# Flyback.net
KiCad netlist of a schematic drawn in Altium Designer
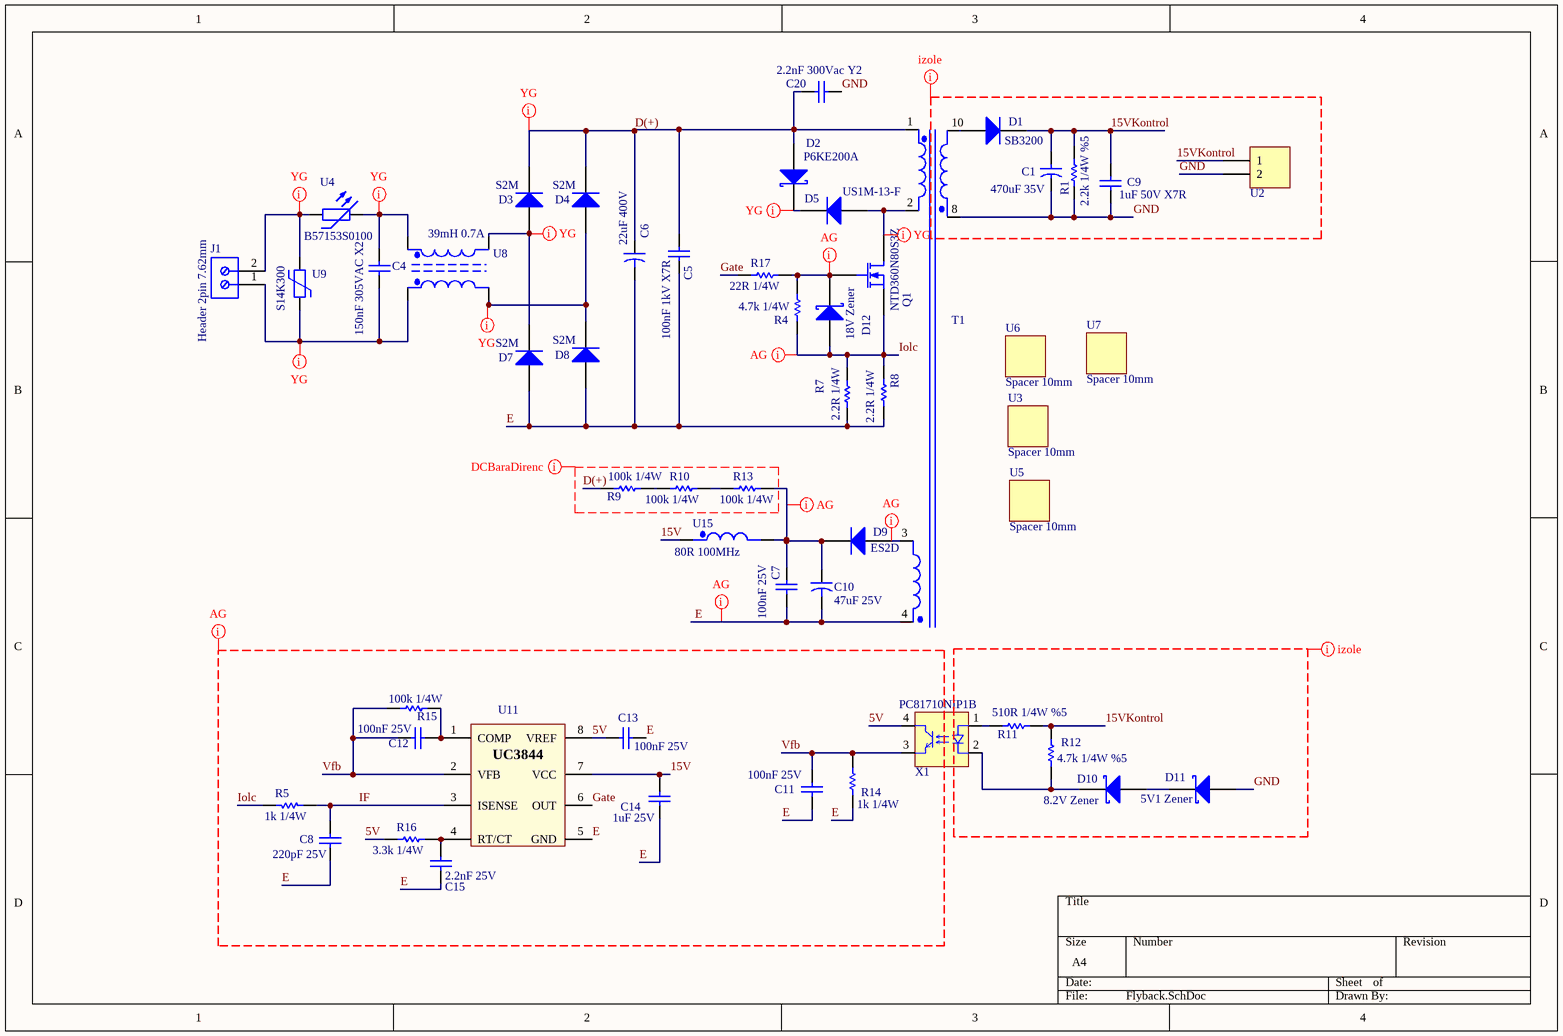
[diagram p0: Flyback.SchDoc]

(export (version "E")
  (design (tool "Eeschema 10.0.6"))
  (components
    (comp (ref "C1")
      (value "470uF 35V")
      (footprint "CAPPRD500W60D1025H1750")
      (description "860040475008")
      (fields (field (name "PUBLISHER") "Altium Limited"))
      (libsource (lib "GenelKutuphane") (part "C 470uF 35V 1.76A 28mOhm"))
    )
    (comp (ref "C4")
      (value "150nF 305VAC X2")
      (footprint "CFR F15 L18 B6 H12")
      (description "MPX154K305E")
      (fields (field (name "PART NUMBER") "890273322005CS") (field (name "PUBLISHER") "Wurth Elektronik"))
      (libsource (lib "GenelKutuphane") (part "Cap 150nF 305VAC X2"))
    )
    (comp (ref "C5")
      (value "100nF 1kV X7R")
      (footprint "RCE7U2J333J5B1H03B")
      (description "RDER73A104K5B1H03B")
      (fields (field (name "PUBLISHER") "Altium Limited"))
      (libsource (lib "GenelKutuphane") (part "C Seramik 100nF 1kV X7R 5mm"))
    )
    (comp (ref "C6")
      (value "22uF 400V")
      (footprint "GenelKutuphane:22uF 400V")
      (description "860241378003")
      (fields
        (field (name "MANUFACTURER_PART_NUMBER") "TPSE107K020R0150")
        (field (name "MOUSER PART NUMBER") "581-TPSE107K020R0150")
      )
      (libsource (lib "GenelKutuphane") (part "C 22uF 400V 537mArms"))
    )
    (comp (ref "C7")
      (value "100nF 25V")
      (footprint "1206")
      (description "SMD 1206")
      (libsource (lib "GenelKutuphane") (part "C 1206"))
    )
    (comp (ref "C8")
      (value "220pF 25V")
      (footprint "1206")
      (description "SMD 1206")
      (libsource (lib "GenelKutuphane") (part "C 1206"))
    )
    (comp (ref "C9")
      (value "1uF 50V X7R")
      (footprint "1206")
      (description "490-3908-2-ND")
      (libsource (lib "GenelKutuphane") (part "C 1206"))
    )
    (comp (ref "C10")
      (value "47uF 25V")
      (footprint "CAPPRD200W50D525H1250")
      (description "25YXJ47MTA5X11")
      (libsource (lib "GenelKutuphane") (part "C 47uF 25V 250mArms 400mOhm"))
    )
    (comp (ref "C11")
      (value "100nF 25V")
      (footprint "1206")
      (description "SMD 1206")
      (libsource (lib "GenelKutuphane") (part "C 1206"))
    )
    (comp (ref "C12")
      (value "100nF 25V")
      (footprint "1206")
      (description "SMD 1206")
      (libsource (lib "GenelKutuphane") (part "C 1206"))
    )
    (comp (ref "C13")
      (value "100nF 25V")
      (footprint "1206")
      (description "SMD 1206")
      (libsource (lib "GenelKutuphane") (part "C 1206"))
    )
    (comp (ref "C14")
      (value "1uF 25V")
      (footprint "1206")
      (description "SMD 1206")
      (libsource (lib "GenelKutuphane") (part "C 1206"))
    )
    (comp (ref "C15")
      (value "2.2nF 25V")
      (footprint "1206")
      (description "SMD 1206")
      (libsource (lib "GenelKutuphane") (part "C 1206"))
    )
    (comp (ref "C20")
      (value "2.2nF 300Vac Y2")
      (footprint "4x13x9")
      (description "B32021A3222")
      (fields (field (name "PUBLISHER") "Altium Limited"))
      (libsource (lib "GenelKutuphane") (part "Cap Y2 2.2nF MKP TDK"))
    )
    (comp (ref "D1")
      (value "SB3200")
      (footprint "GenelKutuphane:DO-201AD -Dik")
      (description "DO-201AD")
      (libsource (lib "GenelKutuphane") (part "D MUR460"))
    )
    (comp (ref "D2")
      (value "P6KE200A")
      (footprint "DO-15((DO-204AC)")
      (description "497-13419-1-ND")
      (fields (field (name "PUBLISHER") "Altium Limited"))
      (libsource (lib "GenelKutuphane") (part "TVS 200V DO-15"))
    )
    (comp (ref "D3")
      (value "S2M")
      (footprint "DO-214AA(SMB)")
      (description "DO-214AA(SMB)")
      (libsource (lib "GenelKutuphane") (part "1N4007"))
    )
    (comp (ref "D4")
      (value "S2M")
      (footprint "DO-214AA(SMB)")
      (description "DO-214AA(SMB)")
      (libsource (lib "GenelKutuphane") (part "1N4007"))
    )
    (comp (ref "D5")
      (value "US1M-13-F")
      (footprint "DO-214AA(SMB)")
      (description "US1M-FDICT-ND")
      (libsource (lib "GenelKutuphane") (part "ES2D"))
    )
    (comp (ref "D7")
      (value "S2M")
      (footprint "DO-214AA(SMB)")
      (description "DO-214AA(SMB)")
      (libsource (lib "GenelKutuphane") (part "1N4007"))
    )
    (comp (ref "D8")
      (value "S2M")
      (footprint "DO-214AA(SMB)")
      (description "DO-214AA(SMB)")
      (libsource (lib "GenelKutuphane") (part "1N4007"))
    )
    (comp (ref "D9")
      (value "ES2D")
      (footprint "DO-214AA(SMB)")
      (description "ES2DFSCT-ND")
      (libsource (lib "GenelKutuphane") (part "ES2D"))
    )
    (comp (ref "D10")
      (value "8.2V Zener")
      (footprint "GenelKutuphane:SOD-123")
      (description "SOD-123")
      (fields (field (name "PUBLISHER") "Altium Limited"))
      (libsource (lib "GenelKutuphane") (part "Zener 1/4W"))
    )
    (comp (ref "D11")
      (value "5V1 Zener")
      (footprint "SOD-123")
      (description "SOD-123")
      (fields (field (name "PUBLISHER") "Altium Limited"))
      (libsource (lib "GenelKutuphane") (part "Zener 1W"))
    )
    (comp (ref "D12")
      (value "18V Zener")
      (footprint "GenelKutuphane:SOD-123")
      (description "SOD-123")
      (fields (field (name "PUBLISHER") "Altium Limited"))
      (libsource (lib "GenelKutuphane") (part "Zener 0.5W"))
    )
    (comp (ref "J1")
      (value "Header 2pin 7.62mm")
      (footprint "Header 2 Pin 7.62mm Vidalı")
      (description "691214410002")
      (fields (field (name "PART NUMBER") "691218410002") (field (name "PUBLISHER") "Wurth Elektronik"))
      (libsource (lib "GenelKutuphane") (part "Header 2pin 7.62mm Vidalı"))
    )
    (comp (ref "Q1")
      (value "NTD360N80S3Z")
      (footprint "DPAK IGBT")
      (description "DPAK")
      (fields (field (name "PUBLISHER") "Altium Limited"))
      (libsource (lib "GenelKutuphane") (part "MOSFET DPAK"))
    )
    (comp (ref "R1")
      (value "2.2k 1/4W %5")
      (footprint "R 1206")
      (description "311-2.2KERTR-ND")
      (libsource (lib "GenelKutuphane") (part "R 1206"))
    )
    (comp (ref "R4")
      (value "4.7k 1/4W")
      (footprint "R 1206")
      (description "SMD 1206")
      (libsource (lib "GenelKutuphane") (part "1/4W Karbon"))
    )
    (comp (ref "R5")
      (value "1k 1/4W")
      (footprint "R 1206")
      (description "SMD 1206/RC1206JR-07330RL/Digikey")
      (libsource (lib "GenelKutuphane") (part "R 1206"))
    )
    (comp (ref "R7")
      (value "2.2R 1/4W")
      (footprint "R 1206")
      (description "SMD 1206")
      (libsource (lib "GenelKutuphane") (part "R 1206"))
    )
    (comp (ref "R8")
      (value "2.2R 1/4W")
      (footprint "R 1206")
      (description "SMD 1206")
      (libsource (lib "GenelKutuphane") (part "R 1206"))
    )
    (comp (ref "R9")
      (value "100k 1/4W")
      (footprint "R 1206")
      (description "SMD 126")
      (libsource (lib "ramazanlib") (part "R 1206"))
    )
    (comp (ref "R10")
      (value "100k 1/4W")
      (footprint "R 1206")
      (description "SMD 126")
      (libsource (lib "ramazanlib") (part "R 1206"))
    )
    (comp (ref "R11")
      (value "510R 1/4W %5")
      (footprint "R 1206")
      (description "311-100NLCT-ND")
      (libsource (lib "GenelKutuphane") (part "R 1206"))
    )
    (comp (ref "R12")
      (value "4.7k 1/4W %5")
      (footprint "R 1206")
      (description "311-4.7KERCT-ND")
      (libsource (lib "GenelKutuphane") (part "R 1206"))
    )
    (comp (ref "R13")
      (value "100k 1/4W")
      (footprint "R 1206")
      (description "SMD 126")
      (libsource (lib "ramazanlib") (part "R 1206"))
    )
    (comp (ref "R14")
      (value "1k 1/4W")
      (footprint "R 1206")
      (description "SMD 1206")
      (libsource (lib "GenelKutuphane") (part "R 1206"))
    )
    (comp (ref "R15")
      (value "100k 1/4W")
      (footprint "R 1206")
      (description "SMD 1206")
      (libsource (lib "GenelKutuphane") (part "R 1206"))
    )
    (comp (ref "R16")
      (value "3.3k 1/4W")
      (footprint "R 1206")
      (description "SMD 1206")
      (libsource (lib "GenelKutuphane") (part "R 1206"))
    )
    (comp (ref "R17")
      (value "22R 1/4W")
      (footprint "R 1206")
      (description "SMD 1206")
      (libsource (lib "ramazanlib") (part "R 1206"))
    )
    (comp (ref "T1")
      (value "SMPS Tr")
      (footprint "SMPS Tr3")
      (fields (field (name "PUBLISHER") "Altium Limited"))
      (libsource (lib "GenelKutuphane") (part "SMPS Tr EF25"))
    )
    (comp (ref "U2")
      (value "Terminal Blok 2 Pin 2.54mm")
      (footprint "Header 2pin 2.54mm Vidalı")
      (description "691210910002")
      (fields (field (name "PUBLISHER") "Altium Limited"))
      (libsource (lib "GenelKutuphane") (part "Header 2 Pin 2.54mm Vidalı"))
    )
    (comp (ref "U3")
      (value "Spacer 10mm")
      (footprint "Spacer 10mm Sogutucu")
      (description "10mm")
      (fields (field (name "PUBLISHER") "Altium Limited"))
      (libsource (lib "GenelKutuphane") (part "Spacer 10mm"))
    )
    (comp (ref "U4")
      (value "B57153S0100")
      (footprint "NTC B57153S0100")
      (description "495-2076-ND")
      (fields (field (name "PUBLISHER") "Altium Limited"))
      (libsource (lib "GenelKutuphane") (part "NTC B57153S0100"))
    )
    (comp (ref "U5")
      (value "Spacer 10mm")
      (footprint "Spacer 10mm Sogutucu")
      (description "10mm")
      (fields (field (name "PUBLISHER") "Altium Limited"))
      (libsource (lib "GenelKutuphane") (part "Spacer 10mm"))
    )
    (comp (ref "U6")
      (value "Spacer 10mm")
      (footprint "Spacer 10mm Sogutucu")
      (description "10mm")
      (fields (field (name "PUBLISHER") "Altium Limited"))
      (libsource (lib "GenelKutuphane") (part "Spacer 10mm"))
    )
    (comp (ref "U7")
      (value "Spacer 10mm")
      (footprint "Spacer 10mm Sogutucu")
      (description "10mm")
      (fields (field (name "PUBLISHER") "Altium Limited"))
      (libsource (lib "GenelKutuphane") (part "Spacer 10mm"))
    )
    (comp (ref "U8")
      (value "39mH 0.7A")
      (footprint "EMC SMPS TDK")
      (description "B82732R2701B030")
      (libsource (lib "GenelKutuphane") (part "EMC SMPS TDK 39mH 0.7A"))
    )
    (comp (ref "U9")
      (value "S14K300")
      (footprint "GenelKutuphane:Varistor630V")
      (description "495-1442-ND")
      (fields (field (name "PUBLISHER") "Altium Limited"))
      (libsource (lib "GenelKutuphane") (part "Varistor  S14K175"))
    )
    (comp (ref "U11")
      (value "UC3844")
      (footprint "SOIC-OA8_L")
      (description "SOIC8")
      (libsource (lib "GenelKutuphane") (part "UC3844"))
    )
    (comp (ref "U15")
      (value "80R 100MHz")
      (footprint "1206 Bead")
      (description "732-1629-1-ND")
      (libsource (lib "GenelKutuphane") (part "Bead 1206"))
    )
    (comp (ref "X1")
      (value "PC81710NIP1B")
      (footprint "PC817 SMD")
      (description "1855-1014-1-ND")
      (libsource (lib "GenelKutuphane") (part "PC817"))
    )
  )
  (nets
    (net (code "1") (name "/5V") (class "Default")
      (node (ref "C13") (pin "2") (pinfunction "2_2") (pintype "passive"))
      (node (ref "R16") (pin "1") (pinfunction "1_1") (pintype "passive"))
      (node (ref "U11") (pin "8") (pinfunction "VREF_8") (pintype "passive"))
      (node (ref "X1") (pin "4") (pinfunction "C_4") (pintype "passive"))
    )
    (net (code "2") (name "/15V") (class "Default")
      (node (ref "C14") (pin "2") (pinfunction "2_2") (pintype "passive"))
      (node (ref "U11") (pin "7") (pinfunction "VCC_7") (pintype "passive"))
      (node (ref "U15") (pin "1") (pinfunction "1_1") (pintype "passive"))
    )
    (net (code "3") (name "/15VKontrol") (class "Default")
      (node (ref "C1") (pin "1") (pinfunction "1_1") (pintype "passive"))
      (node (ref "C9") (pin "2") (pinfunction "2_2") (pintype "passive"))
      (node (ref "D1") (pin "2") (pinfunction "K_2") (pintype "passive"))
      (node (ref "R1") (pin "2") (pinfunction "2_2") (pintype "passive"))
      (node (ref "R11") (pin "1") (pinfunction "1_1") (pintype "passive"))
      (node (ref "R12") (pin "1") (pinfunction "1_1") (pintype "passive"))
      (node (ref "U2") (pin "1") (pinfunction "1_1") (pintype "passive"))
    )
    (net (code "4") (name "/D(+)") (class "Default")
      (node (ref "C20") (pin "1") (pinfunction "1_1") (pintype "passive"))
      (node (ref "C5") (pin "2") (pinfunction "2_2") (pintype "passive"))
      (node (ref "C6") (pin "1") (pinfunction "1_1") (pintype "passive"))
      (node (ref "D2") (pin "1") (pinfunction "A_1") (pintype "passive"))
      (node (ref "D3") (pin "2") (pinfunction "K_2") (pintype "passive"))
      (node (ref "D4") (pin "2") (pinfunction "K_2") (pintype "passive"))
      (node (ref "R9") (pin "2") (pinfunction "2_2") (pintype "passive"))
      (node (ref "T1") (pin "1") (pinfunction "Pri+_1") (pintype "passive"))
    )
    (net (code "5") (name "/E") (class "Default")
      (node (ref "C10") (pin "2") (pinfunction "2_2") (pintype "passive"))
      (node (ref "C11") (pin "1") (pinfunction "1_1") (pintype "passive"))
      (node (ref "C13") (pin "1") (pinfunction "1_1") (pintype "passive"))
      (node (ref "C14") (pin "1") (pinfunction "1_1") (pintype "passive"))
      (node (ref "C15") (pin "1") (pinfunction "1_1") (pintype "passive"))
      (node (ref "C5") (pin "1") (pinfunction "1_1") (pintype "passive"))
      (node (ref "C6") (pin "2") (pinfunction "2_2") (pintype "passive"))
      (node (ref "C7") (pin "1") (pinfunction "1_1") (pintype "passive"))
      (node (ref "C8") (pin "1") (pinfunction "1_1") (pintype "passive"))
      (node (ref "D7") (pin "1") (pinfunction "A_1") (pintype "passive"))
      (node (ref "D8") (pin "1") (pinfunction "A_1") (pintype "passive"))
      (node (ref "R14") (pin "1") (pinfunction "1_1") (pintype "passive"))
      (node (ref "R7") (pin "1") (pinfunction "1_1") (pintype "passive"))
      (node (ref "R8") (pin "1") (pinfunction "1_1") (pintype "passive"))
      (node (ref "T1") (pin "4") (pinfunction "Sec3-_4") (pintype "passive"))
      (node (ref "U11") (pin "5") (pinfunction "GND_5") (pintype "power_in"))
    )
    (net (code "6") (name "/GND") (class "Default")
      (node (ref "C1") (pin "2") (pinfunction "2_2") (pintype "passive"))
      (node (ref "C20") (pin "2") (pinfunction "2_2") (pintype "passive"))
      (node (ref "C9") (pin "1") (pinfunction "1_1") (pintype "passive"))
      (node (ref "D11") (pin "1") (pinfunction "A_1") (pintype "passive"))
      (node (ref "R1") (pin "1") (pinfunction "1_1") (pintype "passive"))
      (node (ref "T1") (pin "8") (pinfunction "8_8") (pintype "passive"))
      (node (ref "U2") (pin "2") (pinfunction "2_2") (pintype "passive"))
    )
    (net (code "7") (name "/Gate") (class "Default")
      (node (ref "R17") (pin "1") (pinfunction "1_1") (pintype "passive"))
      (node (ref "U11") (pin "6") (pinfunction "OUT_6") (pintype "power_in"))
    )
    (net (code "8") (name "/IF") (class "Default")
      (node (ref "C8") (pin "2") (pinfunction "2_2") (pintype "passive"))
      (node (ref "R5") (pin "1") (pinfunction "1_1") (pintype "passive"))
      (node (ref "U11") (pin "3") (pinfunction "ISENSE_3") (pintype "passive"))
    )
    (net (code "9") (name "/Iolc") (class "Default")
      (node (ref "D12") (pin "1") (pinfunction "A_1") (pintype "passive"))
      (node (ref "Q1") (pin "3") (pinfunction "S_3") (pintype "passive"))
      (node (ref "R4") (pin "2") (pinfunction "2_2") (pintype "passive"))
      (node (ref "R5") (pin "2") (pinfunction "2_2") (pintype "passive"))
      (node (ref "R7") (pin "2") (pinfunction "2_2") (pintype "passive"))
      (node (ref "R8") (pin "2") (pinfunction "2_2") (pintype "passive"))
    )
    (net (code "10") (name "/Vfb") (class "Default")
      (node (ref "C11") (pin "2") (pinfunction "2_2") (pintype "passive"))
      (node (ref "C12") (pin "1") (pinfunction "1_1") (pintype "passive"))
      (node (ref "R14") (pin "2") (pinfunction "2_2") (pintype "passive"))
      (node (ref "R15") (pin "1") (pinfunction "1_1") (pintype "passive"))
      (node (ref "U11") (pin "2") (pinfunction "VFB_2") (pintype "passive"))
      (node (ref "X1") (pin "3") (pinfunction "E_3") (pintype "passive"))
    )
    (net (code "11") (name "Net-(C4-Pad1)") (class "Default")
      (node (ref "C4") (pin "1") (pinfunction "1_1") (pintype "passive"))
      (node (ref "J1") (pin "1") (pinfunction "1_1") (pintype "passive"))
      (node (ref "U8") (pin "1") (pinfunction "1_1") (pintype "passive"))
      (node (ref "U9") (pin "1") (pinfunction "1_1") (pintype "passive"))
    )
    (net (code "12") (name "Net-(C4-Pad2)") (class "Default")
      (node (ref "C4") (pin "2") (pinfunction "2_2") (pintype "passive"))
      (node (ref "U4") (pin "2") (pinfunction "2_2") (pintype "passive"))
      (node (ref "U8") (pin "2") (pinfunction "2_2") (pintype "passive"))
    )
    (net (code "13") (name "Net-(D1-A)") (class "Default")
      (node (ref "D1") (pin "1") (pinfunction "A_1") (pintype "passive"))
      (node (ref "T1") (pin "10") (pinfunction "Sec1+_10") (pintype "passive"))
    )
    (net (code "14") (name "Net-(D2-K)") (class "Default")
      (node (ref "D2") (pin "2") (pinfunction "K_2") (pintype "passive"))
      (node (ref "D5") (pin "2") (pinfunction "K_2") (pintype "passive"))
    )
    (net (code "15") (name "Net-(D3-A)") (class "Default")
      (node (ref "D3") (pin "1") (pinfunction "A_1") (pintype "passive"))
      (node (ref "D7") (pin "2") (pinfunction "K_2") (pintype "passive"))
      (node (ref "U8") (pin "3") (pinfunction "3_3") (pintype "passive"))
    )
    (net (code "16") (name "Net-(D4-A)") (class "Default")
      (node (ref "D4") (pin "1") (pinfunction "A_1") (pintype "passive"))
      (node (ref "D8") (pin "2") (pinfunction "K_2") (pintype "passive"))
      (node (ref "U8") (pin "4") (pinfunction "4_4") (pintype "passive"))
    )
    (net (code "17") (name "Net-(D5-A)") (class "Default")
      (node (ref "D5") (pin "1") (pinfunction "A_1") (pintype "passive"))
      (node (ref "Q1") (pin "2") (pinfunction "D_2") (pintype "passive"))
      (node (ref "T1") (pin "2") (pinfunction "Pri-_2") (pintype "passive"))
    )
    (net (code "18") (name "Net-(D9-A)") (class "Default")
      (node (ref "D9") (pin "1") (pinfunction "A_1") (pintype "passive"))
      (node (ref "T1") (pin "3") (pinfunction "Sec3+_3") (pintype "passive"))
    )
    (net (code "19") (name "Net-(D9-K)") (class "Default")
      (node (ref "C10") (pin "1") (pinfunction "1_1") (pintype "passive"))
      (node (ref "C7") (pin "2") (pinfunction "2_2") (pintype "passive"))
      (node (ref "D9") (pin "2") (pinfunction "K_2") (pintype "passive"))
      (node (ref "R13") (pin "1") (pinfunction "1_1") (pintype "passive"))
      (node (ref "U15") (pin "2") (pinfunction "2_2") (pintype "passive"))
    )
    (net (code "20") (name "Net-(D10-A)") (class "Default")
      (node (ref "D10") (pin "1") (pinfunction "A_1") (pintype "passive"))
      (node (ref "D11") (pin "2") (pinfunction "K_2") (pintype "passive"))
    )
    (net (code "21") (name "Net-(D10-K)") (class "Default")
      (node (ref "D10") (pin "2") (pinfunction "K_2") (pintype "passive"))
      (node (ref "R12") (pin "2") (pinfunction "2_2") (pintype "passive"))
      (node (ref "X1") (pin "2") (pinfunction "K_2") (pintype "passive"))
    )
    (net (code "22") (name "Net-(D12-K)") (class "Default")
      (node (ref "D12") (pin "2") (pinfunction "K_2") (pintype "passive"))
      (node (ref "Q1") (pin "1") (pinfunction "G_1") (pintype "passive"))
      (node (ref "R17") (pin "2") (pinfunction "2_2") (pintype "passive"))
      (node (ref "R4") (pin "1") (pinfunction "1_1") (pintype "passive"))
    )
    (net (code "23") (name "Net-(J1-Pad2)") (class "Default")
      (node (ref "J1") (pin "2") (pinfunction "2_2") (pintype "passive"))
      (node (ref "U4") (pin "1") (pinfunction "1_1") (pintype "passive"))
      (node (ref "U9") (pin "2") (pinfunction "2_2") (pintype "passive"))
    )
    (net (code "24") (name "Net-(R10-Pad1)") (class "Default")
      (node (ref "R10") (pin "1") (pinfunction "1_1") (pintype "passive"))
      (node (ref "R13") (pin "2") (pinfunction "2_2") (pintype "passive"))
    )
    (net (code "25") (name "Net-(R10-Pad2)") (class "Default")
      (node (ref "R10") (pin "2") (pinfunction "2_2") (pintype "passive"))
      (node (ref "R9") (pin "1") (pinfunction "1_1") (pintype "passive"))
    )
    (net (code "26") (name "Net-(U11-COMP)") (class "Default")
      (node (ref "C12") (pin "2") (pinfunction "2_2") (pintype "passive"))
      (node (ref "R15") (pin "2") (pinfunction "2_2") (pintype "passive"))
      (node (ref "U11") (pin "1") (pinfunction "COMP_1") (pintype "power_in"))
    )
    (net (code "27") (name "Net-(U11-RT{slash}CT)") (class "Default")
      (node (ref "C15") (pin "2") (pinfunction "2_2") (pintype "passive"))
      (node (ref "R16") (pin "2") (pinfunction "2_2") (pintype "passive"))
      (node (ref "U11") (pin "4") (pinfunction "RT/CT_4") (pintype "power_in"))
    )
    (net (code "28") (name "Net-(X1-A)") (class "Default")
      (node (ref "R11") (pin "2") (pinfunction "2_2") (pintype "passive"))
      (node (ref "X1") (pin "1") (pinfunction "A_1") (pintype "passive"))
    )
  )
)
